# SSOP-20.net
KiCad netlist of a schematic drawn in EAGLE
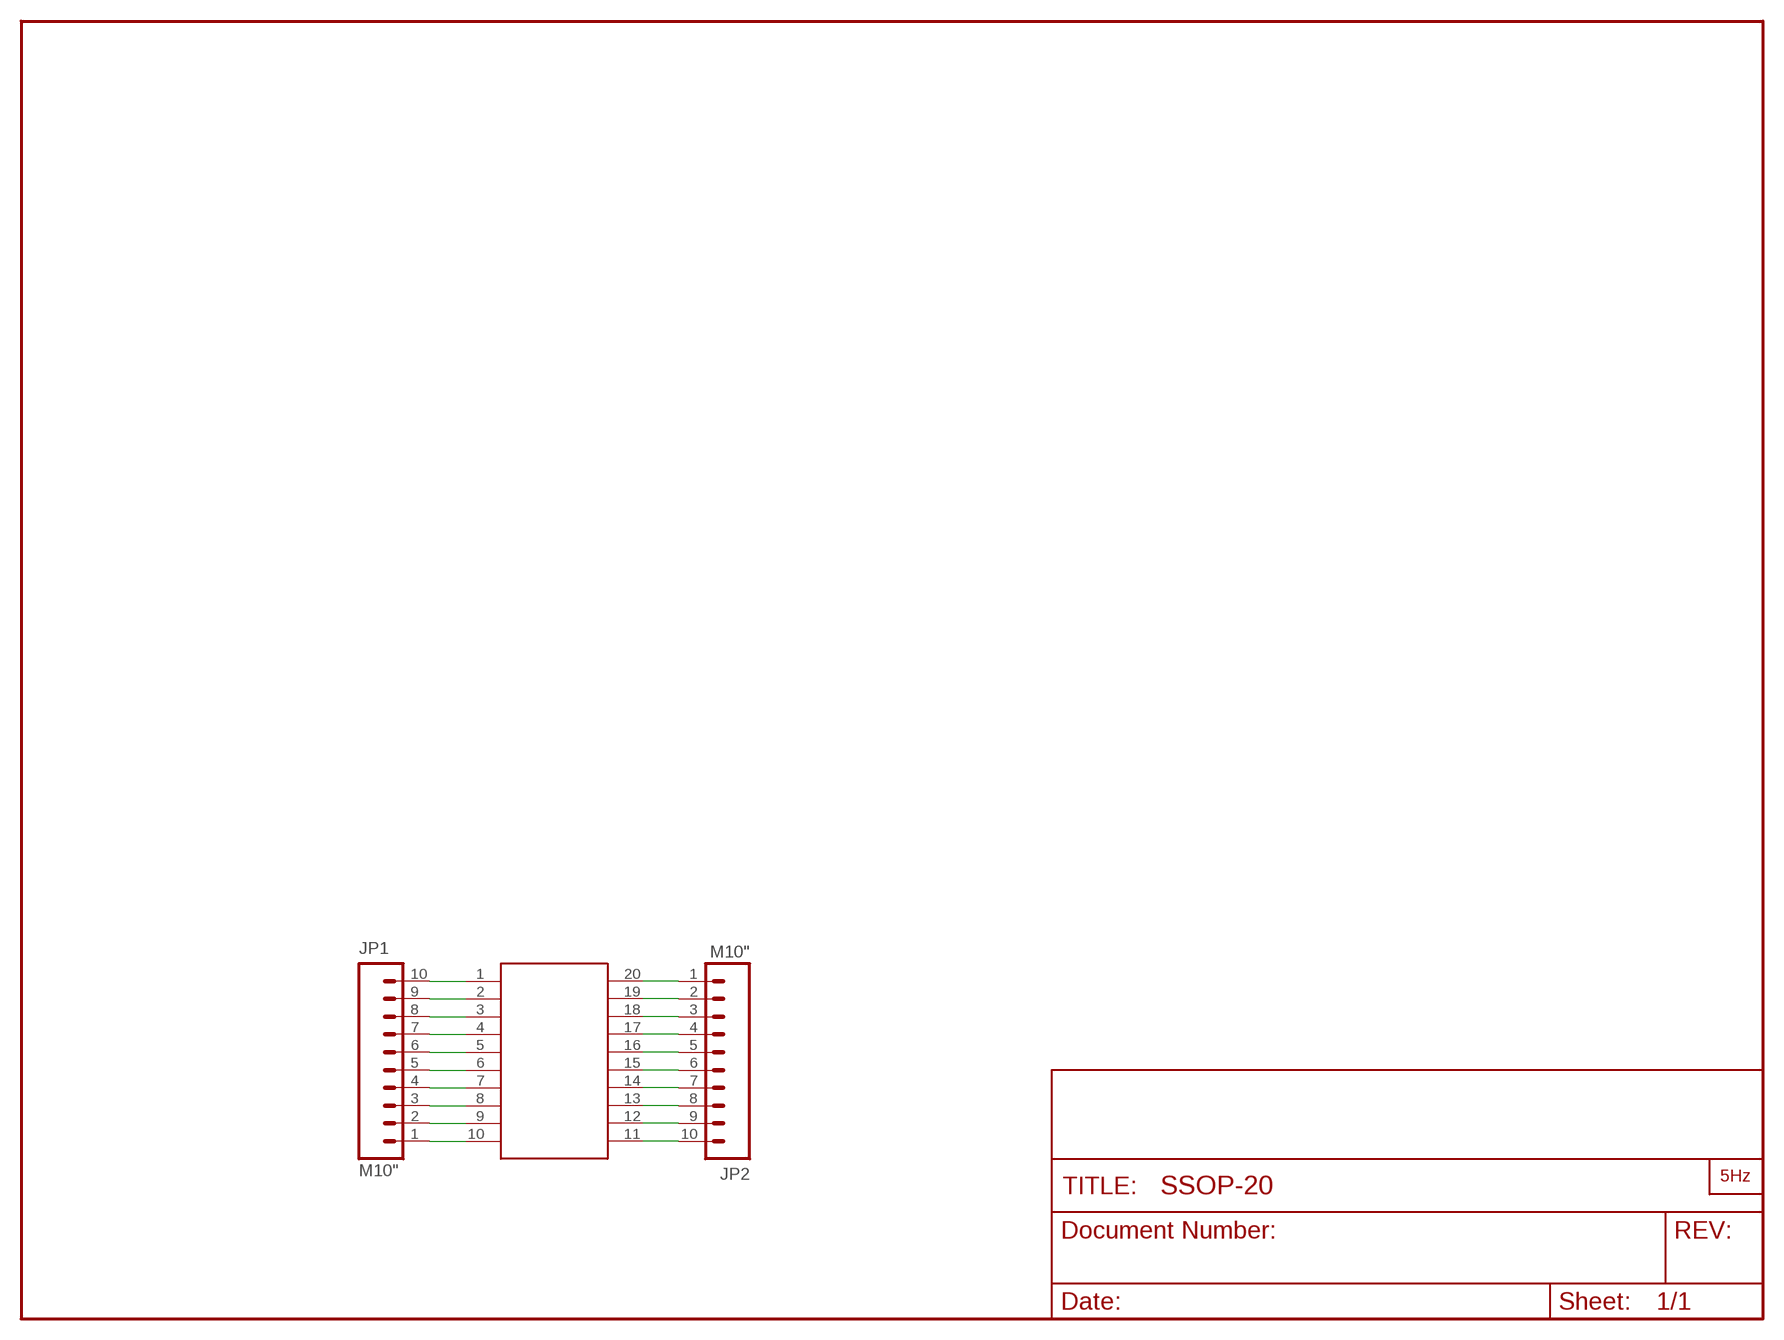
[diagram p0: schematic, sheet 1]

(export (version "E")
  (design (tool "Eeschema 10.0.6"))
  (components
    (comp (ref "JP1")
      (value "M10\"")
      (footprint "eagle-import:1X10")
      (libsource (lib "eagle-import") (part "M10{dblquote}"))
    )
    (comp (ref "JP2")
      (value "M10\"")
      (footprint "eagle-import:1X10")
      (libsource (lib "eagle-import") (part "M10{dblquote}"))
    )
    (comp (ref "U$1")
      (value "SSOP-20SSOP-20")
      (footprint "eagle-import:SSOP-20")
      (libsource (lib "eagle-import") (part "SSOP-20SSOP-20"))
    )
    (comp (ref "U$2")
      (value "LOGO2_SILK10MM")
      (footprint "eagle-import:LOGO2_10MM")
      (libsource (lib "eagle-import") (part "LOGO2_SILK10MM"))
    )
  )
  (nets
    (net (code "1") (name "Net-(U$1-P$1)") (class "Default")
      (node (ref "JP1") (pin "10") (pinfunction "10_10") (pintype "passive"))
      (node (ref "U$1") (pin "1") (pinfunction "P$1_1") (pintype "bidirectional"))
    )
    (net (code "2") (name "Net-(U$1-P$2)") (class "Default")
      (node (ref "JP1") (pin "9") (pinfunction "9_9") (pintype "passive"))
      (node (ref "U$1") (pin "2") (pinfunction "P$2_2") (pintype "bidirectional"))
    )
    (net (code "3") (name "Net-(U$1-P$3)") (class "Default")
      (node (ref "JP1") (pin "8") (pinfunction "8_8") (pintype "passive"))
      (node (ref "U$1") (pin "3") (pinfunction "P$3_3") (pintype "bidirectional"))
    )
    (net (code "4") (name "Net-(U$1-P$4)") (class "Default")
      (node (ref "JP1") (pin "7") (pinfunction "7_7") (pintype "passive"))
      (node (ref "U$1") (pin "4") (pinfunction "P$4_4") (pintype "bidirectional"))
    )
    (net (code "5") (name "Net-(U$1-P$5)") (class "Default")
      (node (ref "JP1") (pin "6") (pinfunction "6_6") (pintype "passive"))
      (node (ref "U$1") (pin "5") (pinfunction "P$5_5") (pintype "bidirectional"))
    )
    (net (code "6") (name "Net-(U$1-P$6)") (class "Default")
      (node (ref "JP1") (pin "5") (pinfunction "5_5") (pintype "passive"))
      (node (ref "U$1") (pin "6") (pinfunction "P$6_6") (pintype "bidirectional"))
    )
    (net (code "7") (name "Net-(U$1-P$7)") (class "Default")
      (node (ref "JP1") (pin "4") (pinfunction "4_4") (pintype "passive"))
      (node (ref "U$1") (pin "7") (pinfunction "P$7_7") (pintype "bidirectional"))
    )
    (net (code "8") (name "Net-(U$1-P$8)") (class "Default")
      (node (ref "JP1") (pin "3") (pinfunction "3_3") (pintype "passive"))
      (node (ref "U$1") (pin "8") (pinfunction "P$8_8") (pintype "bidirectional"))
    )
    (net (code "9") (name "Net-(U$1-P$9)") (class "Default")
      (node (ref "JP1") (pin "2") (pinfunction "2_2") (pintype "passive"))
      (node (ref "U$1") (pin "9") (pinfunction "P$9_9") (pintype "bidirectional"))
    )
    (net (code "10") (name "Net-(U$1-P$10)") (class "Default")
      (node (ref "JP1") (pin "1") (pinfunction "1_1") (pintype "passive"))
      (node (ref "U$1") (pin "10") (pinfunction "P$10_10") (pintype "bidirectional"))
    )
    (net (code "11") (name "Net-(U$1-P$11)") (class "Default")
      (node (ref "JP2") (pin "10") (pinfunction "10_10") (pintype "passive"))
      (node (ref "U$1") (pin "11") (pinfunction "P$11_11") (pintype "bidirectional"))
    )
    (net (code "12") (name "Net-(U$1-P$12)") (class "Default")
      (node (ref "JP2") (pin "9") (pinfunction "9_9") (pintype "passive"))
      (node (ref "U$1") (pin "12") (pinfunction "P$12_12") (pintype "bidirectional"))
    )
    (net (code "13") (name "Net-(U$1-P$13)") (class "Default")
      (node (ref "JP2") (pin "8") (pinfunction "8_8") (pintype "passive"))
      (node (ref "U$1") (pin "13") (pinfunction "P$13_13") (pintype "bidirectional"))
    )
    (net (code "14") (name "Net-(U$1-P$14)") (class "Default")
      (node (ref "JP2") (pin "7") (pinfunction "7_7") (pintype "passive"))
      (node (ref "U$1") (pin "14") (pinfunction "P$14_14") (pintype "bidirectional"))
    )
    (net (code "15") (name "Net-(U$1-P$15)") (class "Default")
      (node (ref "JP2") (pin "6") (pinfunction "6_6") (pintype "passive"))
      (node (ref "U$1") (pin "15") (pinfunction "P$15_15") (pintype "bidirectional"))
    )
    (net (code "16") (name "Net-(U$1-P$16)") (class "Default")
      (node (ref "JP2") (pin "5") (pinfunction "5_5") (pintype "passive"))
      (node (ref "U$1") (pin "16") (pinfunction "P$16_16") (pintype "bidirectional"))
    )
    (net (code "17") (name "Net-(U$1-P$17)") (class "Default")
      (node (ref "JP2") (pin "4") (pinfunction "4_4") (pintype "passive"))
      (node (ref "U$1") (pin "17") (pinfunction "P$17_17") (pintype "bidirectional"))
    )
    (net (code "18") (name "Net-(U$1-P$18)") (class "Default")
      (node (ref "JP2") (pin "3") (pinfunction "3_3") (pintype "passive"))
      (node (ref "U$1") (pin "18") (pinfunction "P$18_18") (pintype "bidirectional"))
    )
    (net (code "19") (name "Net-(U$1-P$19)") (class "Default")
      (node (ref "JP2") (pin "2") (pinfunction "2_2") (pintype "passive"))
      (node (ref "U$1") (pin "19") (pinfunction "P$19_19") (pintype "bidirectional"))
    )
    (net (code "20") (name "Net-(U$1-P$20)") (class "Default")
      (node (ref "JP2") (pin "1") (pinfunction "1_1") (pintype "passive"))
      (node (ref "U$1") (pin "20") (pinfunction "P$20_20") (pintype "bidirectional"))
    )
  )
)
